# P10_DDRC_D_NOVTT.net
KiCad netlist of a schematic drawn in Altium Designer
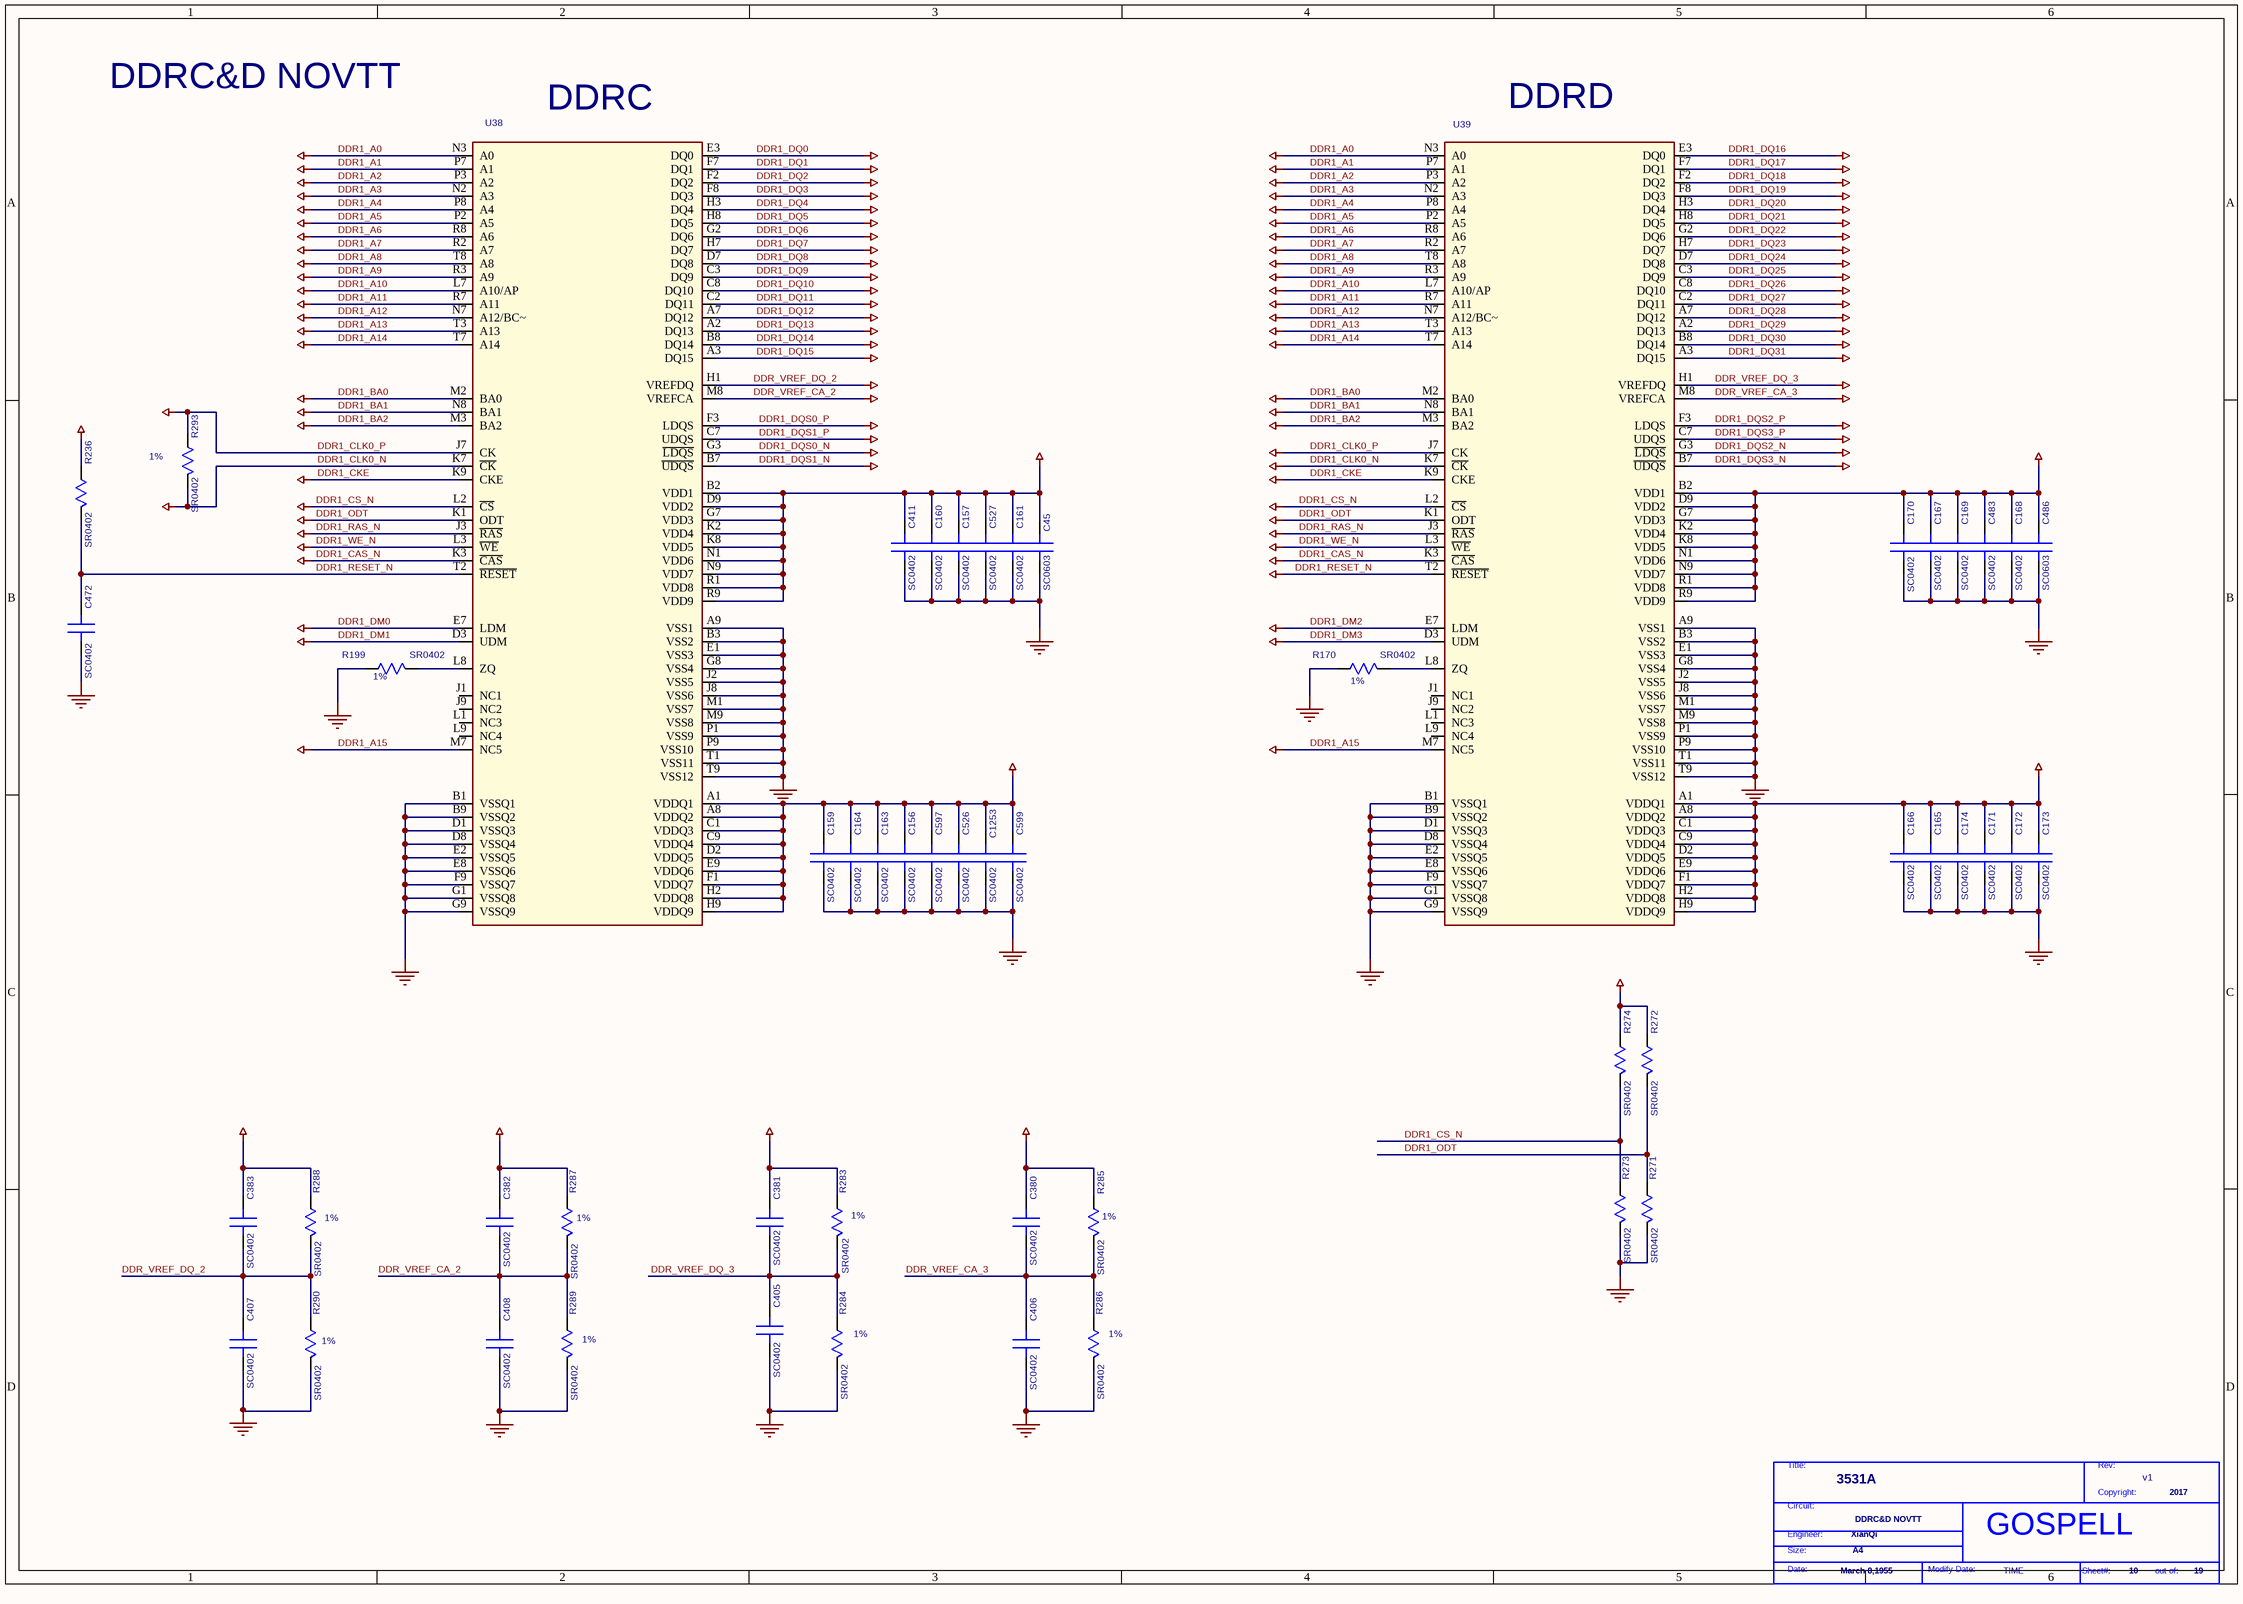
[diagram p0: P10 DDRC&D NOVTT.SchDoc]

(export (version "E")
  (design (tool "Eeschema 10.0.6"))
  (components
    (comp (ref "C45") (value "SC0603") (libsource (lib "*") (part "C_0_Dup2")))
    (comp (ref "C156") (value "SC0402") (libsource (lib "*") (part "C_0_Dup2")))
    (comp (ref "C157") (value "SC0402") (libsource (lib "*") (part "C_0_Dup2")))
    (comp (ref "C159") (value "SC0402") (libsource (lib "*") (part "C_0_Dup2")))
    (comp (ref "C160") (value "SC0402") (libsource (lib "*") (part "C_0_Dup2")))
    (comp (ref "C161") (value "SC0402") (libsource (lib "*") (part "C_0_Dup2")))
    (comp (ref "C163") (value "SC0402") (libsource (lib "*") (part "C_0_Dup2")))
    (comp (ref "C164") (value "SC0402") (libsource (lib "*") (part "C_0_Dup2")))
    (comp (ref "C165") (value "SC0402") (libsource (lib "*") (part "C_0_Dup2")))
    (comp (ref "C166") (value "SC0402") (libsource (lib "*") (part "C_0_Dup2")))
    (comp (ref "C167") (value "SC0402") (libsource (lib "*") (part "C_0_Dup2")))
    (comp (ref "C168") (value "SC0402") (libsource (lib "*") (part "C_0_Dup2")))
    (comp (ref "C169") (value "SC0402") (libsource (lib "*") (part "C_0_Dup2")))
    (comp (ref "C170") (value "SC0402") (libsource (lib "*") (part "C_0_Dup2")))
    (comp (ref "C171") (value "SC0402") (libsource (lib "*") (part "C_0_Dup2")))
    (comp (ref "C172") (value "SC0402") (libsource (lib "*") (part "C_0_Dup2")))
    (comp (ref "C173") (value "SC0402") (libsource (lib "*") (part "C_0_Dup2")))
    (comp (ref "C174") (value "SC0402") (libsource (lib "*") (part "C_0_Dup2")))
    (comp (ref "C380") (value "SC0402") (libsource (lib "*") (part "C_0_Dup2")))
    (comp (ref "C381") (value "SC0402") (libsource (lib "*") (part "C_0_Dup2")))
    (comp (ref "C382") (value "SC0402") (libsource (lib "*") (part "C_0_Dup2")))
    (comp (ref "C383") (value "SC0402") (libsource (lib "*") (part "C_0_Dup2")))
    (comp (ref "C405") (value "SC0402") (libsource (lib "*") (part "C_0_Dup2")))
    (comp (ref "C406") (value "SC0402") (libsource (lib "*") (part "C_0_Dup2")))
    (comp (ref "C407") (value "SC0402") (libsource (lib "*") (part "C_0_Dup2")))
    (comp (ref "C408") (value "SC0402") (libsource (lib "*") (part "C_0_Dup2")))
    (comp (ref "C411") (value "SC0402") (libsource (lib "*") (part "C_0_Dup2")))
    (comp (ref "C472") (value "SC0402") (libsource (lib "*") (part "C_0_Dup2")))
    (comp (ref "C483") (value "SC0402") (libsource (lib "*") (part "C_0_Dup2")))
    (comp (ref "C486") (value "SC0603") (libsource (lib "*") (part "C_0_Dup2")))
    (comp (ref "C526") (value "SC0402") (libsource (lib "*") (part "C_0_Dup2")))
    (comp (ref "C527") (value "SC0402") (libsource (lib "*") (part "C_0_Dup2")))
    (comp (ref "C597") (value "SC0402") (libsource (lib "*") (part "C_0_Dup2")))
    (comp (ref "C599") (value "SC0402") (libsource (lib "*") (part "C_0_Dup2")))
    (comp (ref "C1253") (value "SC0402") (libsource (lib "*") (part "C_0_Dup2")))
    (comp (ref "R170") (value "SR0402") (libsource (lib "*") (part "R_1")))
    (comp (ref "R199") (value "SR0402") (libsource (lib "*") (part "R_1")))
    (comp (ref "R236") (value "SR0402") (libsource (lib "*") (part "R_1")))
    (comp (ref "R271") (value "SR0402") (libsource (lib "*") (part "R_1")))
    (comp (ref "R272") (value "SR0402") (libsource (lib "*") (part "R_1")))
    (comp (ref "R273") (value "SR0402") (libsource (lib "*") (part "R_1")))
    (comp (ref "R274") (value "SR0402") (libsource (lib "*") (part "R_1")))
    (comp (ref "R283") (value "SR0402") (libsource (lib "*") (part "R_1")))
    (comp (ref "R284") (value "SR0402") (libsource (lib "*") (part "R_1")))
    (comp (ref "R285") (value "SR0402") (libsource (lib "*") (part "R_1")))
    (comp (ref "R286") (value "SR0402") (libsource (lib "*") (part "R_1")))
    (comp (ref "R287") (value "SR0402") (libsource (lib "*") (part "R_1")))
    (comp (ref "R288") (value "SR0402") (libsource (lib "*") (part "R_1")))
    (comp (ref "R289") (value "SR0402") (libsource (lib "*") (part "R_1")))
    (comp (ref "R290") (value "SR0402") (libsource (lib "*") (part "R_1")))
    (comp (ref "R293") (value "SR0402") (libsource (lib "*") (part "R_1")))
    (comp (ref "U38") (value "BGA96-32-1609M") (libsource (lib "*") (part "MT41J256M16RE-15E-D_2")))
    (comp (ref "U39") (value "BGA96-32-1609M") (libsource (lib "*") (part "MT41J256M16RE-15E-D_2")))
  )
  (nets
    (net (code "1") (name "1V5") (class "Default")
      (node (ref "C1253") (pin "1") (pinfunction "A_1") (pintype "passive"))
      (node (ref "C156") (pin "1") (pinfunction "A_1") (pintype "passive"))
      (node (ref "C157") (pin "1") (pinfunction "A_1") (pintype "passive"))
      (node (ref "C159") (pin "1") (pinfunction "A_1") (pintype "passive"))
      (node (ref "C160") (pin "1") (pinfunction "A_1") (pintype "passive"))
      (node (ref "C161") (pin "1") (pinfunction "A_1") (pintype "passive"))
      (node (ref "C163") (pin "1") (pinfunction "A_1") (pintype "passive"))
      (node (ref "C164") (pin "1") (pinfunction "A_1") (pintype "passive"))
      (node (ref "C165") (pin "1") (pinfunction "A_1") (pintype "passive"))
      (node (ref "C166") (pin "1") (pinfunction "A_1") (pintype "passive"))
      (node (ref "C167") (pin "1") (pinfunction "A_1") (pintype "passive"))
      (node (ref "C168") (pin "1") (pinfunction "A_1") (pintype "passive"))
      (node (ref "C169") (pin "1") (pinfunction "A_1") (pintype "passive"))
      (node (ref "C170") (pin "1") (pinfunction "A_1") (pintype "passive"))
      (node (ref "C171") (pin "1") (pinfunction "A_1") (pintype "passive"))
      (node (ref "C172") (pin "1") (pinfunction "A_1") (pintype "passive"))
      (node (ref "C173") (pin "1") (pinfunction "A_1") (pintype "passive"))
      (node (ref "C174") (pin "1") (pinfunction "A_1") (pintype "passive"))
      (node (ref "C380") (pin "1") (pinfunction "A_1") (pintype "passive"))
      (node (ref "C381") (pin "1") (pinfunction "A_1") (pintype "passive"))
      (node (ref "C382") (pin "1") (pinfunction "A_1") (pintype "passive"))
      (node (ref "C383") (pin "1") (pinfunction "A_1") (pintype "passive"))
      (node (ref "C411") (pin "1") (pinfunction "A_1") (pintype "passive"))
      (node (ref "C45") (pin "1") (pinfunction "A_1") (pintype "passive"))
      (node (ref "C483") (pin "1") (pinfunction "A_1") (pintype "passive"))
      (node (ref "C486") (pin "1") (pinfunction "A_1") (pintype "passive"))
      (node (ref "C526") (pin "1") (pinfunction "A_1") (pintype "passive"))
      (node (ref "C527") (pin "1") (pinfunction "A_1") (pintype "passive"))
      (node (ref "C597") (pin "1") (pinfunction "A_1") (pintype "passive"))
      (node (ref "C599") (pin "1") (pinfunction "A_1") (pintype "passive"))
      (node (ref "R236") (pin "1") (pinfunction "A_1") (pintype "passive"))
      (node (ref "R272") (pin "1") (pinfunction "A_1") (pintype "passive"))
      (node (ref "R274") (pin "1") (pinfunction "A_1") (pintype "passive"))
      (node (ref "R283") (pin "1") (pinfunction "A_1") (pintype "passive"))
      (node (ref "R285") (pin "1") (pinfunction "A_1") (pintype "passive"))
      (node (ref "R287") (pin "1") (pinfunction "A_1") (pintype "passive"))
      (node (ref "R288") (pin "1") (pinfunction "A_1") (pintype "passive"))
      (node (ref "U38") (pin "A1") (pinfunction "VDDQ1_A1") (pintype "passive"))
      (node (ref "U38") (pin "A8") (pinfunction "VDDQ2_A8") (pintype "passive"))
      (node (ref "U38") (pin "B2") (pinfunction "VDD1_B2") (pintype "passive"))
      (node (ref "U38") (pin "C1") (pinfunction "VDDQ3_C1") (pintype "passive"))
      (node (ref "U38") (pin "C9") (pinfunction "VDDQ4_C9") (pintype "passive"))
      (node (ref "U38") (pin "D2") (pinfunction "VDDQ5_D2") (pintype "passive"))
      (node (ref "U38") (pin "D9") (pinfunction "VDD2_D9") (pintype "passive"))
      (node (ref "U38") (pin "E9") (pinfunction "VDDQ6_E9") (pintype "passive"))
      (node (ref "U38") (pin "F1") (pinfunction "VDDQ7_F1") (pintype "passive"))
      (node (ref "U38") (pin "G7") (pinfunction "VDD3_G7") (pintype "passive"))
      (node (ref "U38") (pin "H2") (pinfunction "VDDQ8_H2") (pintype "passive"))
      (node (ref "U38") (pin "H9") (pinfunction "VDDQ9_H9") (pintype "passive"))
      (node (ref "U38") (pin "K2") (pinfunction "VDD4_K2") (pintype "passive"))
      (node (ref "U38") (pin "K8") (pinfunction "VDD5_K8") (pintype "passive"))
      (node (ref "U38") (pin "N1") (pinfunction "VDD6_N1") (pintype "passive"))
      (node (ref "U38") (pin "N9") (pinfunction "VDD7_N9") (pintype "passive"))
      (node (ref "U38") (pin "R1") (pinfunction "VDD8_R1") (pintype "passive"))
      (node (ref "U38") (pin "R9") (pinfunction "VDD9_R9") (pintype "passive"))
      (node (ref "U39") (pin "A1") (pinfunction "VDDQ1_A1") (pintype "passive"))
      (node (ref "U39") (pin "A8") (pinfunction "VDDQ2_A8") (pintype "passive"))
      (node (ref "U39") (pin "B2") (pinfunction "VDD1_B2") (pintype "passive"))
      (node (ref "U39") (pin "C1") (pinfunction "VDDQ3_C1") (pintype "passive"))
      (node (ref "U39") (pin "C9") (pinfunction "VDDQ4_C9") (pintype "passive"))
      (node (ref "U39") (pin "D2") (pinfunction "VDDQ5_D2") (pintype "passive"))
      (node (ref "U39") (pin "D9") (pinfunction "VDD2_D9") (pintype "passive"))
      (node (ref "U39") (pin "E9") (pinfunction "VDDQ6_E9") (pintype "passive"))
      (node (ref "U39") (pin "F1") (pinfunction "VDDQ7_F1") (pintype "passive"))
      (node (ref "U39") (pin "G7") (pinfunction "VDD3_G7") (pintype "passive"))
      (node (ref "U39") (pin "H2") (pinfunction "VDDQ8_H2") (pintype "passive"))
      (node (ref "U39") (pin "H9") (pinfunction "VDDQ9_H9") (pintype "passive"))
      (node (ref "U39") (pin "K2") (pinfunction "VDD4_K2") (pintype "passive"))
      (node (ref "U39") (pin "K8") (pinfunction "VDD5_K8") (pintype "passive"))
      (node (ref "U39") (pin "N1") (pinfunction "VDD6_N1") (pintype "passive"))
      (node (ref "U39") (pin "N9") (pinfunction "VDD7_N9") (pintype "passive"))
      (node (ref "U39") (pin "R1") (pinfunction "VDD8_R1") (pintype "passive"))
      (node (ref "U39") (pin "R9") (pinfunction "VDD9_R9") (pintype "passive"))
    )
    (net (code "2") (name "DDR1_A0") (class "Default")
      (node (ref "U38") (pin "N3") (pinfunction "A0_N3") (pintype "passive"))
      (node (ref "U39") (pin "N3") (pinfunction "A0_N3") (pintype "passive"))
    )
    (net (code "3") (name "DDR1_A1") (class "Default")
      (node (ref "U38") (pin "P7") (pinfunction "A1_P7") (pintype "passive"))
      (node (ref "U39") (pin "P7") (pinfunction "A1_P7") (pintype "passive"))
    )
    (net (code "4") (name "DDR1_A2") (class "Default")
      (node (ref "U38") (pin "P3") (pinfunction "A2_P3") (pintype "passive"))
      (node (ref "U39") (pin "P3") (pinfunction "A2_P3") (pintype "passive"))
    )
    (net (code "5") (name "DDR1_A3") (class "Default")
      (node (ref "U38") (pin "N2") (pinfunction "A3_N2") (pintype "passive"))
      (node (ref "U39") (pin "N2") (pinfunction "A3_N2") (pintype "passive"))
    )
    (net (code "6") (name "DDR1_A4") (class "Default")
      (node (ref "U38") (pin "P8") (pinfunction "A4_P8") (pintype "passive"))
      (node (ref "U39") (pin "P8") (pinfunction "A4_P8") (pintype "passive"))
    )
    (net (code "7") (name "DDR1_A5") (class "Default")
      (node (ref "U38") (pin "P2") (pinfunction "A5_P2") (pintype "passive"))
      (node (ref "U39") (pin "P2") (pinfunction "A5_P2") (pintype "passive"))
    )
    (net (code "8") (name "DDR1_A6") (class "Default")
      (node (ref "U38") (pin "R8") (pinfunction "A6_R8") (pintype "passive"))
      (node (ref "U39") (pin "R8") (pinfunction "A6_R8") (pintype "passive"))
    )
    (net (code "9") (name "DDR1_A7") (class "Default")
      (node (ref "U38") (pin "R2") (pinfunction "A7_R2") (pintype "passive"))
      (node (ref "U39") (pin "R2") (pinfunction "A7_R2") (pintype "passive"))
    )
    (net (code "10") (name "DDR1_A8") (class "Default")
      (node (ref "U38") (pin "T8") (pinfunction "A8_T8") (pintype "passive"))
      (node (ref "U39") (pin "T8") (pinfunction "A8_T8") (pintype "passive"))
    )
    (net (code "11") (name "DDR1_A9") (class "Default")
      (node (ref "U38") (pin "R3") (pinfunction "A9_R3") (pintype "passive"))
      (node (ref "U39") (pin "R3") (pinfunction "A9_R3") (pintype "passive"))
    )
    (net (code "12") (name "DDR1_A10") (class "Default")
      (node (ref "U38") (pin "L7") (pinfunction "A10/AP_L7") (pintype "passive"))
      (node (ref "U39") (pin "L7") (pinfunction "A10/AP_L7") (pintype "passive"))
    )
    (net (code "13") (name "DDR1_A11") (class "Default")
      (node (ref "U38") (pin "R7") (pinfunction "A11_R7") (pintype "passive"))
      (node (ref "U39") (pin "R7") (pinfunction "A11_R7") (pintype "passive"))
    )
    (net (code "14") (name "DDR1_A12") (class "Default")
      (node (ref "U38") (pin "N7") (pinfunction "A12/BC~_N7") (pintype "passive"))
      (node (ref "U39") (pin "N7") (pinfunction "A12/BC~_N7") (pintype "passive"))
    )
    (net (code "15") (name "DDR1_A13") (class "Default")
      (node (ref "U38") (pin "T3") (pinfunction "A13_T3") (pintype "passive"))
      (node (ref "U39") (pin "T3") (pinfunction "A13_T3") (pintype "passive"))
    )
    (net (code "16") (name "DDR1_A14") (class "Default")
      (node (ref "U38") (pin "T7") (pinfunction "A14_T7") (pintype "passive"))
      (node (ref "U39") (pin "T7") (pinfunction "A14_T7") (pintype "passive"))
    )
    (net (code "17") (name "DDR1_A15") (class "Default")
      (node (ref "U38") (pin "M7") (pinfunction "NC5_M7") (pintype "passive"))
      (node (ref "U39") (pin "M7") (pinfunction "NC5_M7") (pintype "passive"))
    )
    (net (code "18") (name "DDR1_BA0") (class "Default")
      (node (ref "U38") (pin "M2") (pinfunction "BA0_M2") (pintype "passive"))
      (node (ref "U39") (pin "M2") (pinfunction "BA0_M2") (pintype "passive"))
    )
    (net (code "19") (name "DDR1_BA1") (class "Default")
      (node (ref "U38") (pin "N8") (pinfunction "BA1_N8") (pintype "passive"))
      (node (ref "U39") (pin "N8") (pinfunction "BA1_N8") (pintype "passive"))
    )
    (net (code "20") (name "DDR1_BA2") (class "Default")
      (node (ref "U38") (pin "M3") (pinfunction "BA2_M3") (pintype "passive"))
      (node (ref "U39") (pin "M3") (pinfunction "BA2_M3") (pintype "passive"))
    )
    (net (code "21") (name "DDR1_CAS_N") (class "Default")
      (node (ref "U38") (pin "K3") (pinfunction "~{CAS}_K3") (pintype "passive"))
      (node (ref "U39") (pin "K3") (pinfunction "~{CAS}_K3") (pintype "passive"))
    )
    (net (code "22") (name "DDR1_CKE") (class "Default")
      (node (ref "U38") (pin "K9") (pinfunction "CKE_K9") (pintype "passive"))
      (node (ref "U39") (pin "K9") (pinfunction "CKE_K9") (pintype "passive"))
    )
    (net (code "23") (name "DDR1_CLK0_N") (class "Default")
      (node (ref "R293") (pin "2") (pinfunction "B_2") (pintype "passive"))
      (node (ref "U38") (pin "K7") (pinfunction "~{CK}_K7") (pintype "passive"))
      (node (ref "U39") (pin "K7") (pinfunction "~{CK}_K7") (pintype "passive"))
    )
    (net (code "24") (name "DDR1_CLK0_P") (class "Default")
      (node (ref "R293") (pin "1") (pinfunction "A_1") (pintype "passive"))
      (node (ref "U38") (pin "J7") (pinfunction "CK_J7") (pintype "passive"))
      (node (ref "U39") (pin "J7") (pinfunction "CK_J7") (pintype "passive"))
    )
    (net (code "25") (name "DDR1_CS_N") (class "Default")
      (node (ref "R273") (pin "1") (pinfunction "A_1") (pintype "passive"))
      (node (ref "R274") (pin "2") (pinfunction "B_2") (pintype "passive"))
      (node (ref "U38") (pin "L2") (pinfunction "~{CS}_L2") (pintype "passive"))
      (node (ref "U39") (pin "L2") (pinfunction "~{CS}_L2") (pintype "passive"))
    )
    (net (code "26") (name "DDR1_DM0") (class "Default")
      (node (ref "U38") (pin "E7") (pinfunction "LDM_E7") (pintype "passive"))
    )
    (net (code "27") (name "DDR1_DM1") (class "Default")
      (node (ref "U38") (pin "D3") (pinfunction "UDM_D3") (pintype "passive"))
    )
    (net (code "28") (name "DDR1_DM2") (class "Default")
      (node (ref "U39") (pin "E7") (pinfunction "LDM_E7") (pintype "passive"))
    )
    (net (code "29") (name "DDR1_DM3") (class "Default")
      (node (ref "U39") (pin "D3") (pinfunction "UDM_D3") (pintype "passive"))
    )
    (net (code "30") (name "DDR1_DQ0") (class "Default")
      (node (ref "U38") (pin "E3") (pinfunction "DQ0_E3") (pintype "passive"))
    )
    (net (code "31") (name "DDR1_DQ1") (class "Default")
      (node (ref "U38") (pin "F7") (pinfunction "DQ1_F7") (pintype "passive"))
    )
    (net (code "32") (name "DDR1_DQ2") (class "Default")
      (node (ref "U38") (pin "F2") (pinfunction "DQ2_F2") (pintype "passive"))
    )
    (net (code "33") (name "DDR1_DQ3") (class "Default")
      (node (ref "U38") (pin "F8") (pinfunction "DQ3_F8") (pintype "passive"))
    )
    (net (code "34") (name "DDR1_DQ4") (class "Default")
      (node (ref "U38") (pin "H3") (pinfunction "DQ4_H3") (pintype "passive"))
    )
    (net (code "35") (name "DDR1_DQ5") (class "Default")
      (node (ref "U38") (pin "H8") (pinfunction "DQ5_H8") (pintype "passive"))
    )
    (net (code "36") (name "DDR1_DQ6") (class "Default")
      (node (ref "U38") (pin "G2") (pinfunction "DQ6_G2") (pintype "passive"))
    )
    (net (code "37") (name "DDR1_DQ7") (class "Default")
      (node (ref "U38") (pin "H7") (pinfunction "DQ7_H7") (pintype "passive"))
    )
    (net (code "38") (name "DDR1_DQ8") (class "Default")
      (node (ref "U38") (pin "D7") (pinfunction "DQ8_D7") (pintype "passive"))
    )
    (net (code "39") (name "DDR1_DQ9") (class "Default")
      (node (ref "U38") (pin "C3") (pinfunction "DQ9_C3") (pintype "passive"))
    )
    (net (code "40") (name "DDR1_DQ10") (class "Default")
      (node (ref "U38") (pin "C8") (pinfunction "DQ10_C8") (pintype "passive"))
    )
    (net (code "41") (name "DDR1_DQ11") (class "Default")
      (node (ref "U38") (pin "C2") (pinfunction "DQ11_C2") (pintype "passive"))
    )
    (net (code "42") (name "DDR1_DQ12") (class "Default")
      (node (ref "U38") (pin "A7") (pinfunction "DQ12_A7") (pintype "passive"))
    )
    (net (code "43") (name "DDR1_DQ13") (class "Default")
      (node (ref "U38") (pin "A2") (pinfunction "DQ13_A2") (pintype "passive"))
    )
    (net (code "44") (name "DDR1_DQ14") (class "Default")
      (node (ref "U38") (pin "B8") (pinfunction "DQ14_B8") (pintype "passive"))
    )
    (net (code "45") (name "DDR1_DQ15") (class "Default")
      (node (ref "U38") (pin "A3") (pinfunction "DQ15_A3") (pintype "passive"))
    )
    (net (code "46") (name "DDR1_DQ16") (class "Default")
      (node (ref "U39") (pin "E3") (pinfunction "DQ0_E3") (pintype "passive"))
    )
    (net (code "47") (name "DDR1_DQ17") (class "Default")
      (node (ref "U39") (pin "F7") (pinfunction "DQ1_F7") (pintype "passive"))
    )
    (net (code "48") (name "DDR1_DQ18") (class "Default")
      (node (ref "U39") (pin "F2") (pinfunction "DQ2_F2") (pintype "passive"))
    )
    (net (code "49") (name "DDR1_DQ19") (class "Default")
      (node (ref "U39") (pin "F8") (pinfunction "DQ3_F8") (pintype "passive"))
    )
    (net (code "50") (name "DDR1_DQ20") (class "Default")
      (node (ref "U39") (pin "H3") (pinfunction "DQ4_H3") (pintype "passive"))
    )
    (net (code "51") (name "DDR1_DQ21") (class "Default")
      (node (ref "U39") (pin "H8") (pinfunction "DQ5_H8") (pintype "passive"))
    )
    (net (code "52") (name "DDR1_DQ22") (class "Default")
      (node (ref "U39") (pin "G2") (pinfunction "DQ6_G2") (pintype "passive"))
    )
    (net (code "53") (name "DDR1_DQ23") (class "Default")
      (node (ref "U39") (pin "H7") (pinfunction "DQ7_H7") (pintype "passive"))
    )
    (net (code "54") (name "DDR1_DQ24") (class "Default")
      (node (ref "U39") (pin "D7") (pinfunction "DQ8_D7") (pintype "passive"))
    )
    (net (code "55") (name "DDR1_DQ25") (class "Default")
      (node (ref "U39") (pin "C3") (pinfunction "DQ9_C3") (pintype "passive"))
    )
    (net (code "56") (name "DDR1_DQ26") (class "Default")
      (node (ref "U39") (pin "C8") (pinfunction "DQ10_C8") (pintype "passive"))
    )
    (net (code "57") (name "DDR1_DQ27") (class "Default")
      (node (ref "U39") (pin "C2") (pinfunction "DQ11_C2") (pintype "passive"))
    )
    (net (code "58") (name "DDR1_DQ28") (class "Default")
      (node (ref "U39") (pin "A7") (pinfunction "DQ12_A7") (pintype "passive"))
    )
    (net (code "59") (name "DDR1_DQ29") (class "Default")
      (node (ref "U39") (pin "A2") (pinfunction "DQ13_A2") (pintype "passive"))
    )
    (net (code "60") (name "DDR1_DQ30") (class "Default")
      (node (ref "U39") (pin "B8") (pinfunction "DQ14_B8") (pintype "passive"))
    )
    (net (code "61") (name "DDR1_DQ31") (class "Default")
      (node (ref "U39") (pin "A3") (pinfunction "DQ15_A3") (pintype "passive"))
    )
    (net (code "62") (name "DDR1_DQS0_N") (class "Default")
      (node (ref "U38") (pin "G3") (pinfunction "~{LDQS}_G3") (pintype "passive"))
    )
    (net (code "63") (name "DDR1_DQS0_P") (class "Default")
      (node (ref "U38") (pin "F3") (pinfunction "LDQS_F3") (pintype "passive"))
    )
    (net (code "64") (name "DDR1_DQS1_N") (class "Default")
      (node (ref "U38") (pin "B7") (pinfunction "~{UDQS}_B7") (pintype "passive"))
    )
    (net (code "65") (name "DDR1_DQS1_P") (class "Default")
      (node (ref "U38") (pin "C7") (pinfunction "UDQS_C7") (pintype "passive"))
    )
    (net (code "66") (name "DDR1_DQS2_N") (class "Default")
      (node (ref "U39") (pin "G3") (pinfunction "~{LDQS}_G3") (pintype "passive"))
    )
    (net (code "67") (name "DDR1_DQS2_P") (class "Default")
      (node (ref "U39") (pin "F3") (pinfunction "LDQS_F3") (pintype "passive"))
    )
    (net (code "68") (name "DDR1_DQS3_N") (class "Default")
      (node (ref "U39") (pin "B7") (pinfunction "~{UDQS}_B7") (pintype "passive"))
    )
    (net (code "69") (name "DDR1_DQS3_P") (class "Default")
      (node (ref "U39") (pin "C7") (pinfunction "UDQS_C7") (pintype "passive"))
    )
    (net (code "70") (name "DDR1_ODT") (class "Default")
      (node (ref "R271") (pin "1") (pinfunction "A_1") (pintype "passive"))
      (node (ref "R272") (pin "2") (pinfunction "B_2") (pintype "passive"))
      (node (ref "U38") (pin "K1") (pinfunction "ODT_K1") (pintype "passive"))
      (node (ref "U39") (pin "K1") (pinfunction "ODT_K1") (pintype "passive"))
    )
    (net (code "71") (name "DDR1_RAS_N") (class "Default")
      (node (ref "U38") (pin "J3") (pinfunction "~{RAS}_J3") (pintype "passive"))
      (node (ref "U39") (pin "J3") (pinfunction "~{RAS}_J3") (pintype "passive"))
    )
    (net (code "72") (name "DDR1_RESET_N") (class "Default")
      (node (ref "C472") (pin "1") (pinfunction "A_1") (pintype "passive"))
      (node (ref "R236") (pin "2") (pinfunction "B_2") (pintype "passive"))
      (node (ref "U38") (pin "T2") (pinfunction "~{RESET}_T2") (pintype "passive"))
      (node (ref "U39") (pin "T2") (pinfunction "~{RESET}_T2") (pintype "passive"))
    )
    (net (code "73") (name "DDR1_WE_N") (class "Default")
      (node (ref "U38") (pin "L3") (pinfunction "~{WE}_L3") (pintype "passive"))
      (node (ref "U39") (pin "L3") (pinfunction "~{WE}_L3") (pintype "passive"))
    )
    (net (code "74") (name "DDR_VREF_CA_2") (class "Default")
      (node (ref "C382") (pin "2") (pinfunction "B_2") (pintype "passive"))
      (node (ref "C408") (pin "1") (pinfunction "A_1") (pintype "passive"))
      (node (ref "R287") (pin "2") (pinfunction "B_2") (pintype "passive"))
      (node (ref "R289") (pin "1") (pinfunction "A_1") (pintype "passive"))
      (node (ref "U38") (pin "M8") (pinfunction "VREFCA_M8") (pintype "passive"))
    )
    (net (code "75") (name "DDR_VREF_CA_3") (class "Default")
      (node (ref "C380") (pin "2") (pinfunction "B_2") (pintype "passive"))
      (node (ref "C406") (pin "1") (pinfunction "A_1") (pintype "passive"))
      (node (ref "R285") (pin "2") (pinfunction "B_2") (pintype "passive"))
      (node (ref "R286") (pin "1") (pinfunction "A_1") (pintype "passive"))
      (node (ref "U39") (pin "M8") (pinfunction "VREFCA_M8") (pintype "passive"))
    )
    (net (code "76") (name "DDR_VREF_DQ_2") (class "Default")
      (node (ref "C383") (pin "2") (pinfunction "B_2") (pintype "passive"))
      (node (ref "C407") (pin "1") (pinfunction "A_1") (pintype "passive"))
      (node (ref "R288") (pin "2") (pinfunction "B_2") (pintype "passive"))
      (node (ref "R290") (pin "1") (pinfunction "A_1") (pintype "passive"))
      (node (ref "U38") (pin "H1") (pinfunction "VREFDQ_H1") (pintype "passive"))
    )
    (net (code "77") (name "DDR_VREF_DQ_3") (class "Default")
      (node (ref "C381") (pin "2") (pinfunction "B_2") (pintype "passive"))
      (node (ref "C405") (pin "1") (pinfunction "A_1") (pintype "passive"))
      (node (ref "R283") (pin "2") (pinfunction "B_2") (pintype "passive"))
      (node (ref "R284") (pin "1") (pinfunction "A_1") (pintype "passive"))
      (node (ref "U39") (pin "H1") (pinfunction "VREFDQ_H1") (pintype "passive"))
    )
    (net (code "78") (name "GND") (class "Default")
      (node (ref "C1253") (pin "2") (pinfunction "B_2") (pintype "passive"))
      (node (ref "C156") (pin "2") (pinfunction "B_2") (pintype "passive"))
      (node (ref "C157") (pin "2") (pinfunction "B_2") (pintype "passive"))
      (node (ref "C159") (pin "2") (pinfunction "B_2") (pintype "passive"))
      (node (ref "C160") (pin "2") (pinfunction "B_2") (pintype "passive"))
      (node (ref "C161") (pin "2") (pinfunction "B_2") (pintype "passive"))
      (node (ref "C163") (pin "2") (pinfunction "B_2") (pintype "passive"))
      (node (ref "C164") (pin "2") (pinfunction "B_2") (pintype "passive"))
      (node (ref "C165") (pin "2") (pinfunction "B_2") (pintype "passive"))
      (node (ref "C166") (pin "2") (pinfunction "B_2") (pintype "passive"))
      (node (ref "C167") (pin "2") (pinfunction "B_2") (pintype "passive"))
      (node (ref "C168") (pin "2") (pinfunction "B_2") (pintype "passive"))
      (node (ref "C169") (pin "2") (pinfunction "B_2") (pintype "passive"))
      (node (ref "C170") (pin "2") (pinfunction "B_2") (pintype "passive"))
      (node (ref "C171") (pin "2") (pinfunction "B_2") (pintype "passive"))
      (node (ref "C172") (pin "2") (pinfunction "B_2") (pintype "passive"))
      (node (ref "C173") (pin "2") (pinfunction "B_2") (pintype "passive"))
      (node (ref "C174") (pin "2") (pinfunction "B_2") (pintype "passive"))
      (node (ref "C405") (pin "2") (pinfunction "B_2") (pintype "passive"))
      (node (ref "C406") (pin "2") (pinfunction "B_2") (pintype "passive"))
      (node (ref "C407") (pin "2") (pinfunction "B_2") (pintype "passive"))
      (node (ref "C408") (pin "2") (pinfunction "B_2") (pintype "passive"))
      (node (ref "C411") (pin "2") (pinfunction "B_2") (pintype "passive"))
      (node (ref "C45") (pin "2") (pinfunction "B_2") (pintype "passive"))
      (node (ref "C472") (pin "2") (pinfunction "B_2") (pintype "passive"))
      (node (ref "C483") (pin "2") (pinfunction "B_2") (pintype "passive"))
      (node (ref "C486") (pin "2") (pinfunction "B_2") (pintype "passive"))
      (node (ref "C526") (pin "2") (pinfunction "B_2") (pintype "passive"))
      (node (ref "C527") (pin "2") (pinfunction "B_2") (pintype "passive"))
      (node (ref "C597") (pin "2") (pinfunction "B_2") (pintype "passive"))
      (node (ref "C599") (pin "2") (pinfunction "B_2") (pintype "passive"))
      (node (ref "R170") (pin "1") (pinfunction "A_1") (pintype "passive"))
      (node (ref "R199") (pin "1") (pinfunction "A_1") (pintype "passive"))
      (node (ref "R271") (pin "2") (pinfunction "B_2") (pintype "passive"))
      (node (ref "R273") (pin "2") (pinfunction "B_2") (pintype "passive"))
      (node (ref "R284") (pin "2") (pinfunction "B_2") (pintype "passive"))
      (node (ref "R286") (pin "2") (pinfunction "B_2") (pintype "passive"))
      (node (ref "R289") (pin "2") (pinfunction "B_2") (pintype "passive"))
      (node (ref "R290") (pin "2") (pinfunction "B_2") (pintype "passive"))
      (node (ref "U38") (pin "A9") (pinfunction "VSS1_A9") (pintype "passive"))
      (node (ref "U38") (pin "B1") (pinfunction "VSSQ1_B1") (pintype "passive"))
      (node (ref "U38") (pin "B3") (pinfunction "VSS2_B3") (pintype "passive"))
      (node (ref "U38") (pin "B9") (pinfunction "VSSQ2_B9") (pintype "passive"))
      (node (ref "U38") (pin "D1") (pinfunction "VSSQ3_D1") (pintype "passive"))
      (node (ref "U38") (pin "D8") (pinfunction "VSSQ4_D8") (pintype "passive"))
      (node (ref "U38") (pin "E1") (pinfunction "VSS3_E1") (pintype "passive"))
      (node (ref "U38") (pin "E2") (pinfunction "VSSQ5_E2") (pintype "passive"))
      (node (ref "U38") (pin "E8") (pinfunction "VSSQ6_E8") (pintype "passive"))
      (node (ref "U38") (pin "F9") (pinfunction "VSSQ7_F9") (pintype "passive"))
      (node (ref "U38") (pin "G1") (pinfunction "VSSQ8_G1") (pintype "passive"))
      (node (ref "U38") (pin "G8") (pinfunction "VSS4_G8") (pintype "passive"))
      (node (ref "U38") (pin "G9") (pinfunction "VSSQ9_G9") (pintype "passive"))
      (node (ref "U38") (pin "J2") (pinfunction "VSS5_J2") (pintype "passive"))
      (node (ref "U38") (pin "J8") (pinfunction "VSS6_J8") (pintype "passive"))
      (node (ref "U38") (pin "M1") (pinfunction "VSS7_M1") (pintype "passive"))
      (node (ref "U38") (pin "M9") (pinfunction "VSS8_M9") (pintype "passive"))
      (node (ref "U38") (pin "P1") (pinfunction "VSS9_P1") (pintype "passive"))
      (node (ref "U38") (pin "P9") (pinfunction "VSS10_P9") (pintype "passive"))
      (node (ref "U38") (pin "T1") (pinfunction "VSS11_T1") (pintype "passive"))
      (node (ref "U38") (pin "T9") (pinfunction "VSS12_T9") (pintype "passive"))
      (node (ref "U39") (pin "A9") (pinfunction "VSS1_A9") (pintype "passive"))
      (node (ref "U39") (pin "B1") (pinfunction "VSSQ1_B1") (pintype "passive"))
      (node (ref "U39") (pin "B3") (pinfunction "VSS2_B3") (pintype "passive"))
      (node (ref "U39") (pin "B9") (pinfunction "VSSQ2_B9") (pintype "passive"))
      (node (ref "U39") (pin "D1") (pinfunction "VSSQ3_D1") (pintype "passive"))
      (node (ref "U39") (pin "D8") (pinfunction "VSSQ4_D8") (pintype "passive"))
      (node (ref "U39") (pin "E1") (pinfunction "VSS3_E1") (pintype "passive"))
      (node (ref "U39") (pin "E2") (pinfunction "VSSQ5_E2") (pintype "passive"))
      (node (ref "U39") (pin "E8") (pinfunction "VSSQ6_E8") (pintype "passive"))
      (node (ref "U39") (pin "F9") (pinfunction "VSSQ7_F9") (pintype "passive"))
      (node (ref "U39") (pin "G1") (pinfunction "VSSQ8_G1") (pintype "passive"))
      (node (ref "U39") (pin "G8") (pinfunction "VSS4_G8") (pintype "passive"))
      (node (ref "U39") (pin "G9") (pinfunction "VSSQ9_G9") (pintype "passive"))
      (node (ref "U39") (pin "J2") (pinfunction "VSS5_J2") (pintype "passive"))
      (node (ref "U39") (pin "J8") (pinfunction "VSS6_J8") (pintype "passive"))
      (node (ref "U39") (pin "M1") (pinfunction "VSS7_M1") (pintype "passive"))
      (node (ref "U39") (pin "M9") (pinfunction "VSS8_M9") (pintype "passive"))
      (node (ref "U39") (pin "P1") (pinfunction "VSS9_P1") (pintype "passive"))
      (node (ref "U39") (pin "P9") (pinfunction "VSS10_P9") (pintype "passive"))
      (node (ref "U39") (pin "T1") (pinfunction "VSS11_T1") (pintype "passive"))
      (node (ref "U39") (pin "T9") (pinfunction "VSS12_T9") (pintype "passive"))
    )
    (net (code "79") (name "Net-(R170-B)") (class "Default")
      (node (ref "R170") (pin "2") (pinfunction "B_2") (pintype "passive"))
      (node (ref "U39") (pin "L8") (pinfunction "ZQ_L8") (pintype "passive"))
    )
    (net (code "80") (name "Net-(R199-B)") (class "Default")
      (node (ref "R199") (pin "2") (pinfunction "B_2") (pintype "passive"))
      (node (ref "U38") (pin "L8") (pinfunction "ZQ_L8") (pintype "passive"))
    )
    (net (code "81") (name "unconnected-(U38-NC1-PadJ1)") (class "Default")
      (node (ref "U38") (pin "J1") (pinfunction "NC1_J1") (pintype "passive"))
    )
    (net (code "82") (name "unconnected-(U38-NC2-PadJ9)") (class "Default")
      (node (ref "U38") (pin "J9") (pinfunction "NC2_J9") (pintype "passive"))
    )
    (net (code "83") (name "unconnected-(U38-NC3-PadL1)") (class "Default")
      (node (ref "U38") (pin "L1") (pinfunction "NC3_L1") (pintype "passive"))
    )
    (net (code "84") (name "unconnected-(U38-NC4-PadL9)") (class "Default")
      (node (ref "U38") (pin "L9") (pinfunction "NC4_L9") (pintype "passive"))
    )
    (net (code "85") (name "unconnected-(U39-NC1-PadJ1)") (class "Default")
      (node (ref "U39") (pin "J1") (pinfunction "NC1_J1") (pintype "passive"))
    )
    (net (code "86") (name "unconnected-(U39-NC2-PadJ9)") (class "Default")
      (node (ref "U39") (pin "J9") (pinfunction "NC2_J9") (pintype "passive"))
    )
    (net (code "87") (name "unconnected-(U39-NC3-PadL1)") (class "Default")
      (node (ref "U39") (pin "L1") (pinfunction "NC3_L1") (pintype "passive"))
    )
    (net (code "88") (name "unconnected-(U39-NC4-PadL9)") (class "Default")
      (node (ref "U39") (pin "L9") (pinfunction "NC4_L9") (pintype "passive"))
    )
  )
)
